# AS077_DCF77_Empfaenger.net
KiCad netlist of a schematic drawn in EAGLE
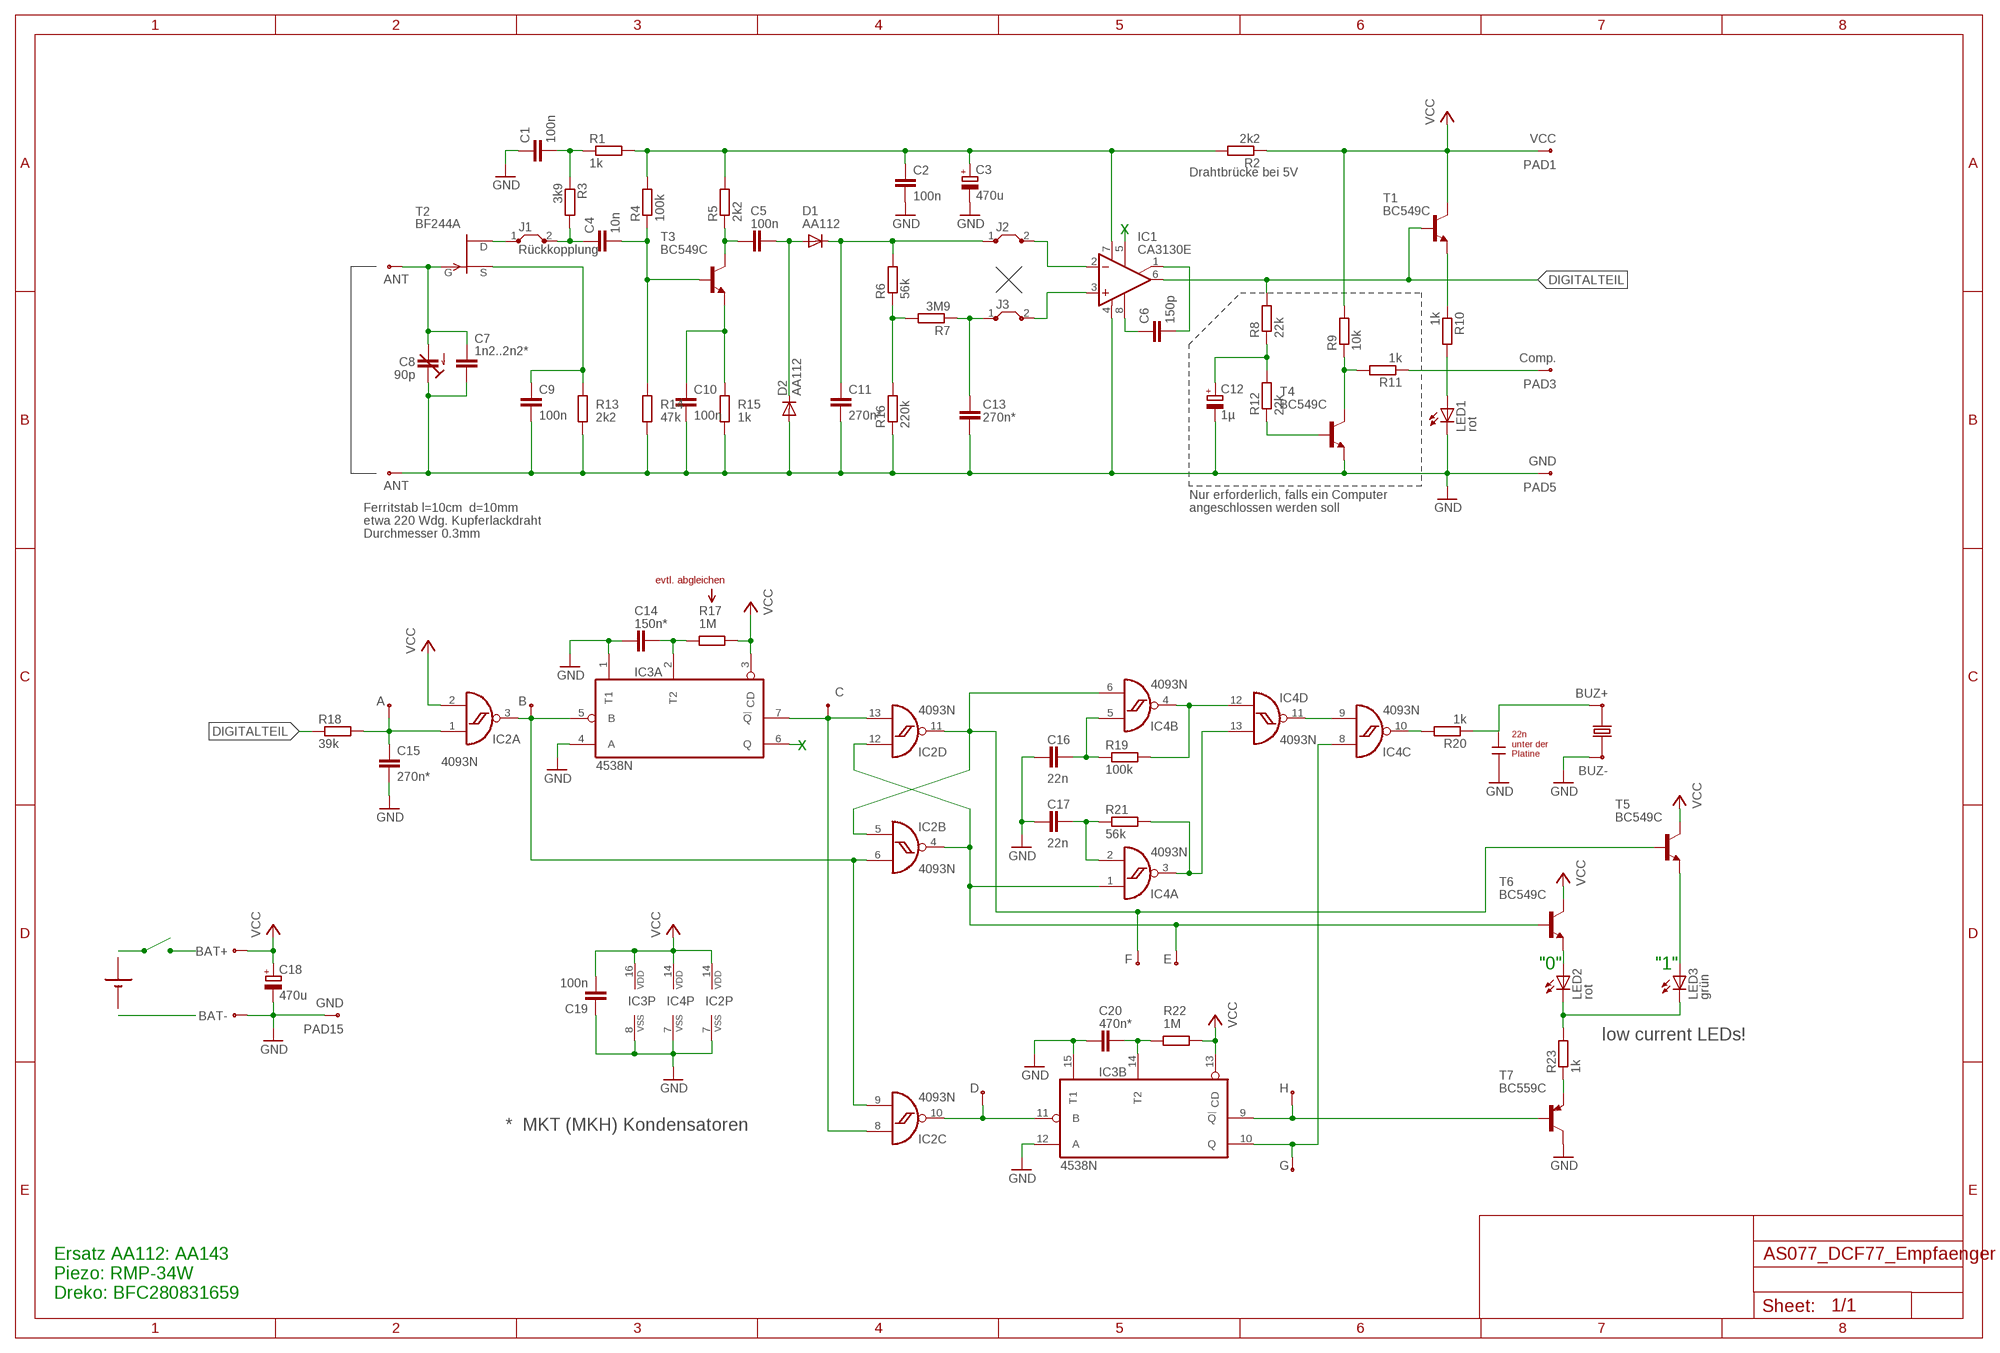
[diagram p0: schematic, sheet 1]

(export (version "E")
  (design (tool "Eeschema 10.0.6"))
  (components
    (comp (ref "C1")
      (value "100n")
      (footprint "eagle-import:RCL_C050-024X044")
      (libsource (lib "eagle-import") (part "RCL_C-EU050-024X044"))
    )
    (comp (ref "C2")
      (value "100n")
      (footprint "eagle-import:RCL_C050-024X044")
      (libsource (lib "eagle-import") (part "RCL_C-EU050-024X044"))
    )
    (comp (ref "C3")
      (value "470u")
      (footprint "eagle-import:RCL_E5-10,5")
      (libsource (lib "eagle-import") (part "RCL_CPOL-EUE5-10.5"))
    )
    (comp (ref "C4")
      (value "10n")
      (footprint "eagle-import:RCL_C050-024X044")
      (libsource (lib "eagle-import") (part "RCL_C-EU050-024X044"))
    )
    (comp (ref "C5")
      (value "100n")
      (footprint "eagle-import:RCL_C050-024X044")
      (libsource (lib "eagle-import") (part "RCL_C-EU050-024X044"))
    )
    (comp (ref "C6")
      (value "150p")
      (footprint "eagle-import:RCL_C050-024X044")
      (libsource (lib "eagle-import") (part "RCL_C-EU050-024X044"))
    )
    (comp (ref "C7")
      (value "1n2..2n2*")
      (footprint "eagle-import:RCL_C075-032X103")
      (libsource (lib "eagle-import") (part "RCL_C-EU075-032X103"))
    )
    (comp (ref "C8")
      (value "90p")
      (footprint "eagle-import:RCL_CTRIM808-BC7.5")
      (libsource (lib "eagle-import") (part "RCL_C-TRIMM808-7.5"))
    )
    (comp (ref "C9")
      (value "100n")
      (footprint "eagle-import:RCL_C050-024X044")
      (libsource (lib "eagle-import") (part "RCL_C-EU050-024X044"))
    )
    (comp (ref "C10")
      (value "100n")
      (footprint "eagle-import:RCL_C050-024X044")
      (libsource (lib "eagle-import") (part "RCL_C-EU050-024X044"))
    )
    (comp (ref "C11")
      (value "270n*")
      (footprint "eagle-import:RCL_C075-032X103")
      (libsource (lib "eagle-import") (part "RCL_C-EU075-032X103"))
    )
    (comp (ref "C12")
      (value "1µ")
      (footprint "eagle-import:E5-6")
      (libsource (lib "eagle-import") (part "RCL_CPOL-EUE5-6"))
    )
    (comp (ref "C13")
      (value "270n*")
      (footprint "eagle-import:RCL_C075-032X103")
      (libsource (lib "eagle-import") (part "RCL_C-EU075-032X103"))
    )
    (comp (ref "C14")
      (value "150n*")
      (footprint "eagle-import:RCL_C075-032X103")
      (libsource (lib "eagle-import") (part "RCL_C-EU075-032X103"))
    )
    (comp (ref "C15")
      (value "270n*")
      (footprint "eagle-import:RCL_C075-032X103")
      (libsource (lib "eagle-import") (part "RCL_C-EU075-032X103"))
    )
    (comp (ref "C16")
      (value "22n")
      (footprint "eagle-import:RCL_C050-024X044")
      (libsource (lib "eagle-import") (part "RCL_C-EU050-024X044"))
    )
    (comp (ref "C17")
      (value "22n")
      (footprint "eagle-import:RCL_C050-024X044")
      (libsource (lib "eagle-import") (part "RCL_C-EU050-024X044"))
    )
    (comp (ref "C18")
      (value "470u")
      (footprint "eagle-import:RCL_E5-10,5")
      (libsource (lib "eagle-import") (part "RCL_CPOL-EUE5-10.5"))
    )
    (comp (ref "C19")
      (value "100n")
      (footprint "eagle-import:RCL_C050-024X044")
      (libsource (lib "eagle-import") (part "RCL_C-EU050-024X044"))
    )
    (comp (ref "C20")
      (value "470n*")
      (footprint "eagle-import:RCL_C075-032X103")
      (libsource (lib "eagle-import") (part "RCL_C-EU075-032X103"))
    )
    (comp (ref "D1")
      (value "AA112")
      (footprint "eagle-import:DIODE_DO07")
      (libsource (lib "eagle-import") (part "DIODE_AA112"))
    )
    (comp (ref "D2")
      (value "AA112")
      (footprint "eagle-import:DIODE_DO07")
      (libsource (lib "eagle-import") (part "DIODE_AA112"))
    )
    (comp (ref "IC1")
      (value "CA3130E")
      (footprint "eagle-import:DIL08")
      (libsource (lib "eagle-import") (part "CA3130N"))
    )
    (comp (ref "IC2")
      (value "4093N")
      (footprint "eagle-import:DIL14")
      (libsource (lib "eagle-import") (part "40XX_4093N"))
    )
    (comp (ref "IC3")
      (value "4538N")
      (footprint "eagle-import:DIL16")
      (libsource (lib "eagle-import") (part "45XX_4538N"))
    )
    (comp (ref "IC4")
      (value "4093N")
      (footprint "eagle-import:DIL14")
      (libsource (lib "eagle-import") (part "40XX_4093N"))
    )
    (comp (ref "J1")
      (value "Rückkopplung")
      (footprint "eagle-import:JUMPER_05")
      (libsource (lib "eagle-import") (part "JUMPER_J5MM"))
    )
    (comp (ref "J2")
      (value "JUMPER_J5MM")
      (footprint "eagle-import:JUMPER_05")
      (libsource (lib "eagle-import") (part "JUMPER_J5MM"))
    )
    (comp (ref "J3")
      (value "JUMPER_J5MM")
      (footprint "eagle-import:JUMPER_05")
      (libsource (lib "eagle-import") (part "JUMPER_J5MM"))
    )
    (comp (ref "LED1")
      (value "rot")
      (footprint "eagle-import:LED_LED5MM")
      (libsource (lib "eagle-import") (part "LED_LED5MM"))
    )
    (comp (ref "LED2")
      (value "rot")
      (footprint "eagle-import:LED_LED5MM")
      (libsource (lib "eagle-import") (part "LED_LED5MM"))
    )
    (comp (ref "LED3")
      (value "grün")
      (footprint "eagle-import:LED_LED5MM")
      (libsource (lib "eagle-import") (part "LED_LED5MM"))
    )
    (comp (ref "PAD1")
      (value "VCC")
      (footprint "eagle-import:WIREPAD_2.2_1.3")
      (libsource (lib "eagle-import") (part "WIREPAD_2.2/1.3"))
    )
    (comp (ref "PAD2")
      (value "ANT")
      (footprint "eagle-import:WIREPAD_2.2_1.3")
      (libsource (lib "eagle-import") (part "WIREPAD_2.2/1.3"))
    )
    (comp (ref "PAD3")
      (value "Comp.")
      (footprint "eagle-import:WIREPAD_2.2_1.3")
      (libsource (lib "eagle-import") (part "WIREPAD_2.2/1.3"))
    )
    (comp (ref "PAD4")
      (value "ANT")
      (footprint "eagle-import:WIREPAD_2.2_1.3")
      (libsource (lib "eagle-import") (part "WIREPAD_2.2/1.3"))
    )
    (comp (ref "PAD5")
      (value "GND")
      (footprint "eagle-import:WIREPAD_2.2_1.3")
      (libsource (lib "eagle-import") (part "WIREPAD_2.2/1.3"))
    )
    (comp (ref "PAD6")
      (value "A")
      (footprint "eagle-import:WIREPAD_2.2_1.3")
      (libsource (lib "eagle-import") (part "WIREPAD_2.2/1.3"))
    )
    (comp (ref "PAD7")
      (value "B")
      (footprint "eagle-import:WIREPAD_2.2_1.3")
      (libsource (lib "eagle-import") (part "WIREPAD_2.2/1.3"))
    )
    (comp (ref "PAD8")
      (value "C")
      (footprint "eagle-import:WIREPAD_2.2_1.3")
      (libsource (lib "eagle-import") (part "WIREPAD_2.2/1.3"))
    )
    (comp (ref "PAD9")
      (value "BUZ-")
      (footprint "eagle-import:WIREPAD_2.2_1.3")
      (libsource (lib "eagle-import") (part "WIREPAD_2.2/1.3"))
    )
    (comp (ref "PAD10")
      (value "BUZ+")
      (footprint "eagle-import:WIREPAD_2.2_1.3")
      (libsource (lib "eagle-import") (part "WIREPAD_2.2/1.3"))
    )
    (comp (ref "PAD11")
      (value "BAT+")
      (footprint "eagle-import:WIREPAD_2.2_1.3")
      (libsource (lib "eagle-import") (part "WIREPAD_2.2/1.3"))
    )
    (comp (ref "PAD12")
      (value "F")
      (footprint "eagle-import:WIREPAD_2.2_1.3")
      (libsource (lib "eagle-import") (part "WIREPAD_2.2/1.3"))
    )
    (comp (ref "PAD13")
      (value "E")
      (footprint "eagle-import:WIREPAD_2.2_1.3")
      (libsource (lib "eagle-import") (part "WIREPAD_2.2/1.3"))
    )
    (comp (ref "PAD14")
      (value "BAT-")
      (footprint "eagle-import:WIREPAD_2.2_1.3")
      (libsource (lib "eagle-import") (part "WIREPAD_2.2/1.3"))
    )
    (comp (ref "PAD15")
      (value "GND")
      (footprint "eagle-import:WIREPAD_2.2_1.3")
      (libsource (lib "eagle-import") (part "WIREPAD_2.2/1.3"))
    )
    (comp (ref "PAD16")
      (value "D")
      (footprint "eagle-import:WIREPAD_2.2_1.3")
      (libsource (lib "eagle-import") (part "WIREPAD_2.2/1.3"))
    )
    (comp (ref "PAD17")
      (value "H")
      (footprint "eagle-import:WIREPAD_2.2_1.3")
      (libsource (lib "eagle-import") (part "WIREPAD_2.2/1.3"))
    )
    (comp (ref "PAD18")
      (value "G")
      (footprint "eagle-import:WIREPAD_2.2_1.3")
      (libsource (lib "eagle-import") (part "WIREPAD_2.2/1.3"))
    )
    (comp (ref "Q1")
      (value "34MM_PIEZO")
      (footprint "eagle-import:34MM_PIEZO_SCREW")
      (libsource (lib "eagle-import") (part "34MM_PIEZO"))
    )
    (comp (ref "R1")
      (value "1k")
      (footprint "eagle-import:RCL_0207_5V")
      (libsource (lib "eagle-import") (part "RCL_R-EU_0207/5V"))
    )
    (comp (ref "R2")
      (value "2k2")
      (footprint "eagle-import:RCL_0207_5V")
      (libsource (lib "eagle-import") (part "RCL_R-EU_0207/5V"))
    )
    (comp (ref "R3")
      (value "3k9")
      (footprint "eagle-import:RCL_0207_15")
      (libsource (lib "eagle-import") (part "RCL_R-EU_0207/15"))
    )
    (comp (ref "R4")
      (value "100k")
      (footprint "eagle-import:RCL_0207_5V")
      (libsource (lib "eagle-import") (part "RCL_R-EU_0207/5V"))
    )
    (comp (ref "R5")
      (value "2k2")
      (footprint "eagle-import:RCL_0207_5V")
      (libsource (lib "eagle-import") (part "RCL_R-EU_0207/5V"))
    )
    (comp (ref "R6")
      (value "56k")
      (footprint "eagle-import:RCL_0207_5V")
      (libsource (lib "eagle-import") (part "RCL_R-EU_0207/5V"))
    )
    (comp (ref "R7")
      (value "3M9")
      (footprint "eagle-import:RCL_0207_5V")
      (libsource (lib "eagle-import") (part "RCL_R-EU_0207/5V"))
    )
    (comp (ref "R8")
      (value "22k")
      (footprint "eagle-import:RCL_0207_5V")
      (libsource (lib "eagle-import") (part "RCL_R-EU_0207/5V"))
    )
    (comp (ref "R9")
      (value "10k")
      (footprint "eagle-import:RCL_0207_5V")
      (libsource (lib "eagle-import") (part "RCL_R-EU_0207/5V"))
    )
    (comp (ref "R10")
      (value "1k")
      (footprint "eagle-import:RCL_0207_5V")
      (libsource (lib "eagle-import") (part "RCL_R-EU_0207/5V"))
    )
    (comp (ref "R11")
      (value "1k")
      (footprint "eagle-import:RCL_0207_5V")
      (libsource (lib "eagle-import") (part "RCL_R-EU_0207/5V"))
    )
    (comp (ref "R12")
      (value "22k")
      (footprint "eagle-import:RCL_0207_5V")
      (libsource (lib "eagle-import") (part "RCL_R-EU_0207/5V"))
    )
    (comp (ref "R13")
      (value "2k2")
      (footprint "eagle-import:RCL_0207_5V")
      (libsource (lib "eagle-import") (part "RCL_R-EU_0207/5V"))
    )
    (comp (ref "R14")
      (value "47k")
      (footprint "eagle-import:RCL_0207_5V")
      (libsource (lib "eagle-import") (part "RCL_R-EU_0207/5V"))
    )
    (comp (ref "R15")
      (value "1k")
      (footprint "eagle-import:RCL_0207_5V")
      (libsource (lib "eagle-import") (part "RCL_R-EU_0207/5V"))
    )
    (comp (ref "R16")
      (value "220k")
      (footprint "eagle-import:RCL_0207_5V")
      (libsource (lib "eagle-import") (part "RCL_R-EU_0207/5V"))
    )
    (comp (ref "R17")
      (value "1M")
      (footprint "eagle-import:RCL_0207_15")
      (libsource (lib "eagle-import") (part "RCL_R-EU_0207/15"))
    )
    (comp (ref "R18")
      (value "39k")
      (footprint "eagle-import:RCL_0207_15")
      (libsource (lib "eagle-import") (part "RCL_R-EU_0207/15"))
    )
    (comp (ref "R19")
      (value "100k")
      (footprint "eagle-import:RCL_0207_5V")
      (libsource (lib "eagle-import") (part "RCL_R-EU_0207/5V"))
    )
    (comp (ref "R20")
      (value "1k")
      (footprint "eagle-import:RCL_0207_5V")
      (libsource (lib "eagle-import") (part "RCL_R-EU_0207/5V"))
    )
    (comp (ref "R21")
      (value "56k")
      (footprint "eagle-import:RCL_0207_5V")
      (libsource (lib "eagle-import") (part "RCL_R-EU_0207/5V"))
    )
    (comp (ref "R22")
      (value "1M")
      (footprint "eagle-import:RCL_0207_15")
      (libsource (lib "eagle-import") (part "RCL_R-EU_0207/15"))
    )
    (comp (ref "R23")
      (value "1k")
      (footprint "eagle-import:RCL_0207_10")
      (libsource (lib "eagle-import") (part "RCL_R-EU_0207/10"))
    )
    (comp (ref "T1")
      (value "BC549C")
      (footprint "eagle-import:TO92_5.08")
      (libsource (lib "eagle-import") (part "BC549C5.08"))
    )
    (comp (ref "T2")
      (value "BF244A")
      (footprint "eagle-import:TO92_5.08")
      (libsource (lib "eagle-import") (part "BF244A5.08"))
    )
    (comp (ref "T3")
      (value "BC549C")
      (footprint "eagle-import:TO92_5.08")
      (libsource (lib "eagle-import") (part "BC549C5.08"))
    )
    (comp (ref "T4")
      (value "BC549C")
      (footprint "eagle-import:TO92_5.08")
      (libsource (lib "eagle-import") (part "BC549C5.08"))
    )
    (comp (ref "T5")
      (value "BC549C")
      (footprint "eagle-import:TO92_2.54")
      (libsource (lib "eagle-import") (part "BC549C2.54"))
    )
    (comp (ref "T6")
      (value "BC549C")
      (footprint "eagle-import:TO92_2.54")
      (libsource (lib "eagle-import") (part "BC549C2.54"))
    )
    (comp (ref "T7")
      (value "BC559C")
      (footprint "eagle-import:TO92_5.08")
      (libsource (lib "eagle-import") (part "BC559C5.08"))
    )
    (comp (ref "U$1")
      (value "9V_SILKSCREEN")
      (footprint "eagle-import:9V_BLOCK")
      (libsource (lib "eagle-import") (part "9V_SILKSCREEN"))
    )
  )
  (nets
    (net (code "1") (name "DIGITALTEIL") (class "Default")
      (node (ref "IC1") (pin "6") (pinfunction "OUT_6") (pintype "output"))
      (node (ref "R18") (pin "1") (pinfunction "1_1") (pintype "passive"))
      (node (ref "R8") (pin "2") (pinfunction "2_2") (pintype "passive"))
      (node (ref "T1") (pin "2") (pinfunction "B_2") (pintype "passive"))
    )
    (net (code "2") (name "GND") (class "Default")
      (node (ref "C1") (pin "1") (pinfunction "1_1") (pintype "passive"))
      (node (ref "C10") (pin "2") (pinfunction "2_2") (pintype "passive"))
      (node (ref "C11") (pin "2") (pinfunction "2_2") (pintype "passive"))
      (node (ref "C12") (pin "-") (pinfunction "-_-") (pintype "passive"))
      (node (ref "C13") (pin "2") (pinfunction "2_2") (pintype "passive"))
      (node (ref "C14") (pin "1") (pinfunction "1_1") (pintype "passive"))
      (node (ref "C15") (pin "2") (pinfunction "2_2") (pintype "passive"))
      (node (ref "C16") (pin "1") (pinfunction "1_1") (pintype "passive"))
      (node (ref "C17") (pin "1") (pinfunction "1_1") (pintype "passive"))
      (node (ref "C18") (pin "-") (pinfunction "-_-") (pintype "passive"))
      (node (ref "C19") (pin "1") (pinfunction "1_1") (pintype "passive"))
      (node (ref "C2") (pin "2") (pinfunction "2_2") (pintype "passive"))
      (node (ref "C20") (pin "1") (pinfunction "1_1") (pintype "passive"))
      (node (ref "C3") (pin "-") (pinfunction "-_-") (pintype "passive"))
      (node (ref "C7") (pin "2") (pinfunction "2_2") (pintype "passive"))
      (node (ref "C8") (pin "1") (pinfunction "E_1") (pintype "passive"))
      (node (ref "C8") (pin "3") (pinfunction "E_3") (pintype "passive"))
      (node (ref "C9") (pin "2") (pinfunction "2_2") (pintype "passive"))
      (node (ref "D2") (pin "A") (pinfunction "A_A") (pintype "passive"))
      (node (ref "IC1") (pin "4") (pinfunction "V-_4") (pintype "power_in"))
      (node (ref "IC2") (pin "7") (pinfunction "VSS_7") (pintype "power_in"))
      (node (ref "IC3") (pin "1") (pinfunction "T1_1") (pintype "input"))
      (node (ref "IC3") (pin "12") (pinfunction "A_12") (pintype "input"))
      (node (ref "IC3") (pin "15") (pinfunction "T1_15") (pintype "input"))
      (node (ref "IC3") (pin "4") (pinfunction "A_4") (pintype "input"))
      (node (ref "IC3") (pin "8") (pinfunction "VSS_8") (pintype "power_in"))
      (node (ref "IC4") (pin "7") (pinfunction "VSS_7") (pintype "power_in"))
      (node (ref "LED1") (pin "K") (pinfunction "C_K") (pintype "passive"))
      (node (ref "PAD14") (pin "1") (pinfunction "P_1") (pintype "passive"))
      (node (ref "PAD15") (pin "1") (pinfunction "P_1") (pintype "passive"))
      (node (ref "PAD4") (pin "1") (pinfunction "P_1") (pintype "passive"))
      (node (ref "PAD5") (pin "1") (pinfunction "P_1") (pintype "passive"))
      (node (ref "PAD9") (pin "1") (pinfunction "P_1") (pintype "passive"))
      (node (ref "R13") (pin "1") (pinfunction "1_1") (pintype "passive"))
      (node (ref "R14") (pin "1") (pinfunction "1_1") (pintype "passive"))
      (node (ref "R15") (pin "1") (pinfunction "1_1") (pintype "passive"))
      (node (ref "R16") (pin "1") (pinfunction "1_1") (pintype "passive"))
      (node (ref "T4") (pin "3") (pinfunction "E_3") (pintype "passive"))
      (node (ref "T7") (pin "1") (pinfunction "C_1") (pintype "passive"))
    )
    (net (code "3") (name "Net-(C1-Pad2)") (class "Default")
      (node (ref "C1") (pin "2") (pinfunction "2_2") (pintype "passive"))
      (node (ref "R1") (pin "1") (pinfunction "1_1") (pintype "passive"))
      (node (ref "R3") (pin "1") (pinfunction "1_1") (pintype "passive"))
    )
    (net (code "4") (name "Net-(C4-Pad1)") (class "Default")
      (node (ref "C4") (pin "1") (pinfunction "1_1") (pintype "passive"))
      (node (ref "J1") (pin "2") (pinfunction "2_2") (pintype "passive"))
      (node (ref "R3") (pin "2") (pinfunction "2_2") (pintype "passive"))
    )
    (net (code "5") (name "Net-(C5-Pad2)") (class "Default")
      (node (ref "C5") (pin "2") (pinfunction "2_2") (pintype "passive"))
      (node (ref "D1") (pin "A") (pinfunction "A_A") (pintype "passive"))
      (node (ref "D2") (pin "C") (pinfunction "C_C") (pintype "passive"))
    )
    (net (code "6") (name "Net-(C8-A)") (class "Default")
      (node (ref "C7") (pin "1") (pinfunction "1_1") (pintype "passive"))
      (node (ref "C8") (pin "2") (pinfunction "A_2") (pintype "passive"))
      (node (ref "PAD2") (pin "1") (pinfunction "P_1") (pintype "passive"))
      (node (ref "T2") (pin "2") (pinfunction "G_2") (pintype "passive"))
    )
    (net (code "7") (name "Net-(C11-Pad1)") (class "Default")
      (node (ref "C11") (pin "1") (pinfunction "1_1") (pintype "passive"))
      (node (ref "D1") (pin "C") (pinfunction "C_C") (pintype "passive"))
      (node (ref "J2") (pin "1") (pinfunction "1_1") (pintype "passive"))
      (node (ref "R6") (pin "2") (pinfunction "2_2") (pintype "passive"))
    )
    (net (code "8") (name "Net-(C12-Pad+)") (class "Default")
      (node (ref "C12") (pin "+") (pinfunction "+_+") (pintype "passive"))
      (node (ref "R12") (pin "2") (pinfunction "2_2") (pintype "passive"))
      (node (ref "R8") (pin "1") (pinfunction "1_1") (pintype "passive"))
    )
    (net (code "9") (name "Net-(C13-Pad1)") (class "Default")
      (node (ref "C13") (pin "1") (pinfunction "1_1") (pintype "passive"))
      (node (ref "J3") (pin "1") (pinfunction "1_1") (pintype "passive"))
      (node (ref "R7") (pin "1") (pinfunction "1_1") (pintype "passive"))
    )
    (net (code "10") (name "Net-(IC1-+IN)") (class "Default")
      (node (ref "IC1") (pin "3") (pinfunction "+IN_3") (pintype "input"))
      (node (ref "J3") (pin "2") (pinfunction "2_2") (pintype "passive"))
    )
    (net (code "11") (name "Net-(IC1--IN)") (class "Default")
      (node (ref "IC1") (pin "2") (pinfunction "-IN_2") (pintype "input"))
      (node (ref "J2") (pin "2") (pinfunction "2_2") (pintype "passive"))
    )
    (net (code "12") (name "Net-(IC1-CMP)") (class "Default")
      (node (ref "C6") (pin "1") (pinfunction "1_1") (pintype "passive"))
      (node (ref "IC1") (pin "8") (pinfunction "CMP_8") (pintype "passive"))
    )
    (net (code "13") (name "Net-(IC1-ON{slash}CMP)") (class "Default")
      (node (ref "C6") (pin "2") (pinfunction "2_2") (pintype "passive"))
      (node (ref "IC1") (pin "1") (pinfunction "ON/CMP_1") (pintype "passive"))
    )
    (net (code "14") (name "Net-(IC1-V+)") (class "Default")
      (node (ref "C2") (pin "1") (pinfunction "1_1") (pintype "passive"))
      (node (ref "C3") (pin "+") (pinfunction "+_+") (pintype "passive"))
      (node (ref "IC1") (pin "7") (pinfunction "V+_7") (pintype "power_in"))
      (node (ref "R1") (pin "2") (pinfunction "2_2") (pintype "passive"))
      (node (ref "R2") (pin "2") (pinfunction "2_2") (pintype "passive"))
      (node (ref "R4") (pin "2") (pinfunction "2_2") (pintype "passive"))
      (node (ref "R5") (pin "2") (pinfunction "2_2") (pintype "passive"))
    )
    (net (code "15") (name "Net-(IC2A-I0)") (class "Default")
      (node (ref "C15") (pin "1") (pinfunction "1_1") (pintype "passive"))
      (node (ref "IC2") (pin "1") (pinfunction "I0_1") (pintype "input"))
      (node (ref "PAD6") (pin "1") (pinfunction "P_1") (pintype "passive"))
      (node (ref "R18") (pin "2") (pinfunction "2_2") (pintype "passive"))
    )
    (net (code "16") (name "Net-(IC2A-O)") (class "Default")
      (node (ref "IC2") (pin "3") (pinfunction "O_3") (pintype "output"))
      (node (ref "IC2") (pin "6") (pinfunction "I1_6") (pintype "input"))
      (node (ref "IC2") (pin "9") (pinfunction "I1_9") (pintype "input"))
      (node (ref "IC3") (pin "5") (pinfunction "B_5") (pintype "input"))
      (node (ref "PAD7") (pin "1") (pinfunction "P_1") (pintype "passive"))
    )
    (net (code "17") (name "Net-(IC2B-I0)") (class "Default")
      (node (ref "IC2") (pin "11") (pinfunction "O_11") (pintype "output"))
      (node (ref "IC2") (pin "5") (pinfunction "I0_5") (pintype "input"))
      (node (ref "IC4") (pin "6") (pinfunction "I1_6") (pintype "input"))
      (node (ref "PAD12") (pin "1") (pinfunction "P_1") (pintype "passive"))
      (node (ref "T5") (pin "2") (pinfunction "B_2") (pintype "passive"))
    )
    (net (code "18") (name "Net-(IC2B-O)") (class "Default")
      (node (ref "IC2") (pin "12") (pinfunction "I0_12") (pintype "input"))
      (node (ref "IC2") (pin "4") (pinfunction "O_4") (pintype "output"))
      (node (ref "IC4") (pin "1") (pinfunction "I0_1") (pintype "input"))
      (node (ref "PAD13") (pin "1") (pinfunction "P_1") (pintype "passive"))
      (node (ref "T6") (pin "2") (pinfunction "B_2") (pintype "passive"))
    )
    (net (code "19") (name "Net-(IC2C-I0)") (class "Default")
      (node (ref "IC2") (pin "13") (pinfunction "I1_13") (pintype "input"))
      (node (ref "IC2") (pin "8") (pinfunction "I0_8") (pintype "input"))
      (node (ref "IC3") (pin "7") (pinfunction "~{Q}_7") (pintype "output"))
      (node (ref "PAD8") (pin "1") (pinfunction "P_1") (pintype "passive"))
    )
    (net (code "20") (name "Net-(IC2C-O)") (class "Default")
      (node (ref "IC2") (pin "10") (pinfunction "O_10") (pintype "output"))
      (node (ref "IC3") (pin "11") (pinfunction "B_11") (pintype "input"))
      (node (ref "PAD16") (pin "1") (pinfunction "P_1") (pintype "passive"))
    )
    (net (code "21") (name "Net-(IC3A-T2)") (class "Default")
      (node (ref "C14") (pin "2") (pinfunction "2_2") (pintype "passive"))
      (node (ref "IC3") (pin "2") (pinfunction "T2_2") (pintype "input"))
      (node (ref "R17") (pin "2") (pinfunction "2_2") (pintype "passive"))
    )
    (net (code "22") (name "Net-(IC3B-Q)") (class "Default")
      (node (ref "IC3") (pin "10") (pinfunction "Q_10") (pintype "output"))
      (node (ref "IC4") (pin "8") (pinfunction "I0_8") (pintype "input"))
      (node (ref "PAD18") (pin "1") (pinfunction "P_1") (pintype "passive"))
    )
    (net (code "23") (name "Net-(IC3B-T2)") (class "Default")
      (node (ref "C20") (pin "2") (pinfunction "2_2") (pintype "passive"))
      (node (ref "IC3") (pin "14") (pinfunction "T2_14") (pintype "input"))
      (node (ref "R22") (pin "2") (pinfunction "2_2") (pintype "passive"))
    )
    (net (code "24") (name "Net-(IC3B-~{Q})") (class "Default")
      (node (ref "IC3") (pin "9") (pinfunction "~{Q}_9") (pintype "output"))
      (node (ref "PAD17") (pin "1") (pinfunction "P_1") (pintype "passive"))
      (node (ref "T7") (pin "2") (pinfunction "B_2") (pintype "passive"))
    )
    (net (code "25") (name "Net-(IC4A-I1)") (class "Default")
      (node (ref "C17") (pin "2") (pinfunction "2_2") (pintype "passive"))
      (node (ref "IC4") (pin "2") (pinfunction "I1_2") (pintype "input"))
      (node (ref "R21") (pin "1") (pinfunction "1_1") (pintype "passive"))
    )
    (net (code "26") (name "Net-(IC4A-O)") (class "Default")
      (node (ref "IC4") (pin "13") (pinfunction "I1_13") (pintype "input"))
      (node (ref "IC4") (pin "3") (pinfunction "O_3") (pintype "output"))
      (node (ref "R21") (pin "2") (pinfunction "2_2") (pintype "passive"))
    )
    (net (code "27") (name "Net-(IC4B-I0)") (class "Default")
      (node (ref "C16") (pin "2") (pinfunction "2_2") (pintype "passive"))
      (node (ref "IC4") (pin "5") (pinfunction "I0_5") (pintype "input"))
      (node (ref "R19") (pin "1") (pinfunction "1_1") (pintype "passive"))
    )
    (net (code "28") (name "Net-(IC4B-O)") (class "Default")
      (node (ref "IC4") (pin "12") (pinfunction "I0_12") (pintype "input"))
      (node (ref "IC4") (pin "4") (pinfunction "O_4") (pintype "output"))
      (node (ref "R19") (pin "2") (pinfunction "2_2") (pintype "passive"))
    )
    (net (code "29") (name "Net-(IC4C-I1)") (class "Default")
      (node (ref "IC4") (pin "11") (pinfunction "O_11") (pintype "output"))
      (node (ref "IC4") (pin "9") (pinfunction "I1_9") (pintype "input"))
    )
    (net (code "30") (name "Net-(IC4C-O)") (class "Default")
      (node (ref "IC4") (pin "10") (pinfunction "O_10") (pintype "output"))
      (node (ref "R20") (pin "2") (pinfunction "2_2") (pintype "passive"))
    )
    (net (code "31") (name "Net-(LED1-PadA)") (class "Default")
      (node (ref "LED1") (pin "A") (pinfunction "A_A") (pintype "passive"))
      (node (ref "R10") (pin "2") (pinfunction "2_2") (pintype "passive"))
    )
    (net (code "32") (name "Net-(LED2-C)") (class "Default")
      (node (ref "LED2") (pin "K") (pinfunction "C_K") (pintype "passive"))
      (node (ref "LED3") (pin "K") (pinfunction "C_K") (pintype "passive"))
      (node (ref "R23") (pin "2") (pinfunction "2_2") (pintype "passive"))
    )
    (net (code "33") (name "Net-(PAD3-P)") (class "Default")
      (node (ref "PAD3") (pin "1") (pinfunction "P_1") (pintype "passive"))
      (node (ref "R11") (pin "1") (pinfunction "1_1") (pintype "passive"))
    )
    (net (code "34") (name "Net-(PAD10-P)") (class "Default")
      (node (ref "PAD10") (pin "1") (pinfunction "P_1") (pintype "passive"))
      (node (ref "R20") (pin "1") (pinfunction "1_1") (pintype "passive"))
    )
    (net (code "35") (name "Net-(R16-Pad2)") (class "Default")
      (node (ref "R16") (pin "2") (pinfunction "2_2") (pintype "passive"))
      (node (ref "R6") (pin "1") (pinfunction "1_1") (pintype "passive"))
      (node (ref "R7") (pin "2") (pinfunction "2_2") (pintype "passive"))
    )
    (net (code "36") (name "Net-(T1-E)") (class "Default")
      (node (ref "R10") (pin "1") (pinfunction "1_1") (pintype "passive"))
      (node (ref "T1") (pin "3") (pinfunction "E_3") (pintype "passive"))
    )
    (net (code "37") (name "Net-(T2-D)") (class "Default")
      (node (ref "J1") (pin "1") (pinfunction "1_1") (pintype "passive"))
      (node (ref "T2") (pin "3") (pinfunction "D_3") (pintype "passive"))
    )
    (net (code "38") (name "Net-(T2-S)") (class "Default")
      (node (ref "C9") (pin "1") (pinfunction "1_1") (pintype "passive"))
      (node (ref "R13") (pin "2") (pinfunction "2_2") (pintype "passive"))
      (node (ref "T2") (pin "1") (pinfunction "S_1") (pintype "passive"))
    )
    (net (code "39") (name "Net-(T3-B)") (class "Default")
      (node (ref "C4") (pin "2") (pinfunction "2_2") (pintype "passive"))
      (node (ref "R14") (pin "2") (pinfunction "2_2") (pintype "passive"))
      (node (ref "R4") (pin "1") (pinfunction "1_1") (pintype "passive"))
      (node (ref "T3") (pin "2") (pinfunction "B_2") (pintype "passive"))
    )
    (net (code "40") (name "Net-(T3-C)") (class "Default")
      (node (ref "C5") (pin "1") (pinfunction "1_1") (pintype "passive"))
      (node (ref "R5") (pin "1") (pinfunction "1_1") (pintype "passive"))
      (node (ref "T3") (pin "1") (pinfunction "C_1") (pintype "passive"))
    )
    (net (code "41") (name "Net-(T3-E)") (class "Default")
      (node (ref "C10") (pin "1") (pinfunction "1_1") (pintype "passive"))
      (node (ref "R15") (pin "2") (pinfunction "2_2") (pintype "passive"))
      (node (ref "T3") (pin "3") (pinfunction "E_3") (pintype "passive"))
    )
    (net (code "42") (name "Net-(T4-B)") (class "Default")
      (node (ref "R12") (pin "1") (pinfunction "1_1") (pintype "passive"))
      (node (ref "T4") (pin "2") (pinfunction "B_2") (pintype "passive"))
    )
    (net (code "43") (name "Net-(T4-C)") (class "Default")
      (node (ref "R11") (pin "2") (pinfunction "2_2") (pintype "passive"))
      (node (ref "R9") (pin "1") (pinfunction "1_1") (pintype "passive"))
      (node (ref "T4") (pin "1") (pinfunction "C_1") (pintype "passive"))
    )
    (net (code "44") (name "Net-(T5-E)") (class "Default")
      (node (ref "LED3") (pin "A") (pinfunction "A_A") (pintype "passive"))
      (node (ref "T5") (pin "3") (pinfunction "E_3") (pintype "passive"))
    )
    (net (code "45") (name "Net-(T6-E)") (class "Default")
      (node (ref "LED2") (pin "A") (pinfunction "A_A") (pintype "passive"))
      (node (ref "T6") (pin "3") (pinfunction "E_3") (pintype "passive"))
    )
    (net (code "46") (name "Net-(T7-E)") (class "Default")
      (node (ref "R23") (pin "1") (pinfunction "1_1") (pintype "passive"))
      (node (ref "T7") (pin "3") (pinfunction "E_3") (pintype "passive"))
    )
    (net (code "47") (name "VCC") (class "Default")
      (node (ref "C18") (pin "+") (pinfunction "+_+") (pintype "passive"))
      (node (ref "C19") (pin "2") (pinfunction "2_2") (pintype "passive"))
      (node (ref "IC2") (pin "14") (pinfunction "VDD_14") (pintype "power_in"))
      (node (ref "IC2") (pin "2") (pinfunction "I1_2") (pintype "input"))
      (node (ref "IC3") (pin "13") (pinfunction "CD_13") (pintype "input"))
      (node (ref "IC3") (pin "16") (pinfunction "VDD_16") (pintype "power_in"))
      (node (ref "IC3") (pin "3") (pinfunction "CD_3") (pintype "input"))
      (node (ref "IC4") (pin "14") (pinfunction "VDD_14") (pintype "power_in"))
      (node (ref "PAD1") (pin "1") (pinfunction "P_1") (pintype "passive"))
      (node (ref "PAD11") (pin "1") (pinfunction "P_1") (pintype "passive"))
      (node (ref "R17") (pin "1") (pinfunction "1_1") (pintype "passive"))
      (node (ref "R2") (pin "1") (pinfunction "1_1") (pintype "passive"))
      (node (ref "R22") (pin "1") (pinfunction "1_1") (pintype "passive"))
      (node (ref "R9") (pin "2") (pinfunction "2_2") (pintype "passive"))
      (node (ref "T1") (pin "1") (pinfunction "C_1") (pintype "passive"))
      (node (ref "T5") (pin "1") (pinfunction "C_1") (pintype "passive"))
      (node (ref "T6") (pin "1") (pinfunction "C_1") (pintype "passive"))
    )
    (net (code "48") (name "unconnected-(IC1-ON-Pad5)") (class "Default")
      (node (ref "IC1") (pin "5") (pinfunction "ON_5") (pintype "passive"))
    )
    (net (code "49") (name "unconnected-(IC3A-Q-Pad6)") (class "Default")
      (node (ref "IC3") (pin "6") (pinfunction "Q_6") (pintype "output"))
    )
  )
)
